# Sheet1.net
KiCad netlist of a schematic drawn in Altium Designer
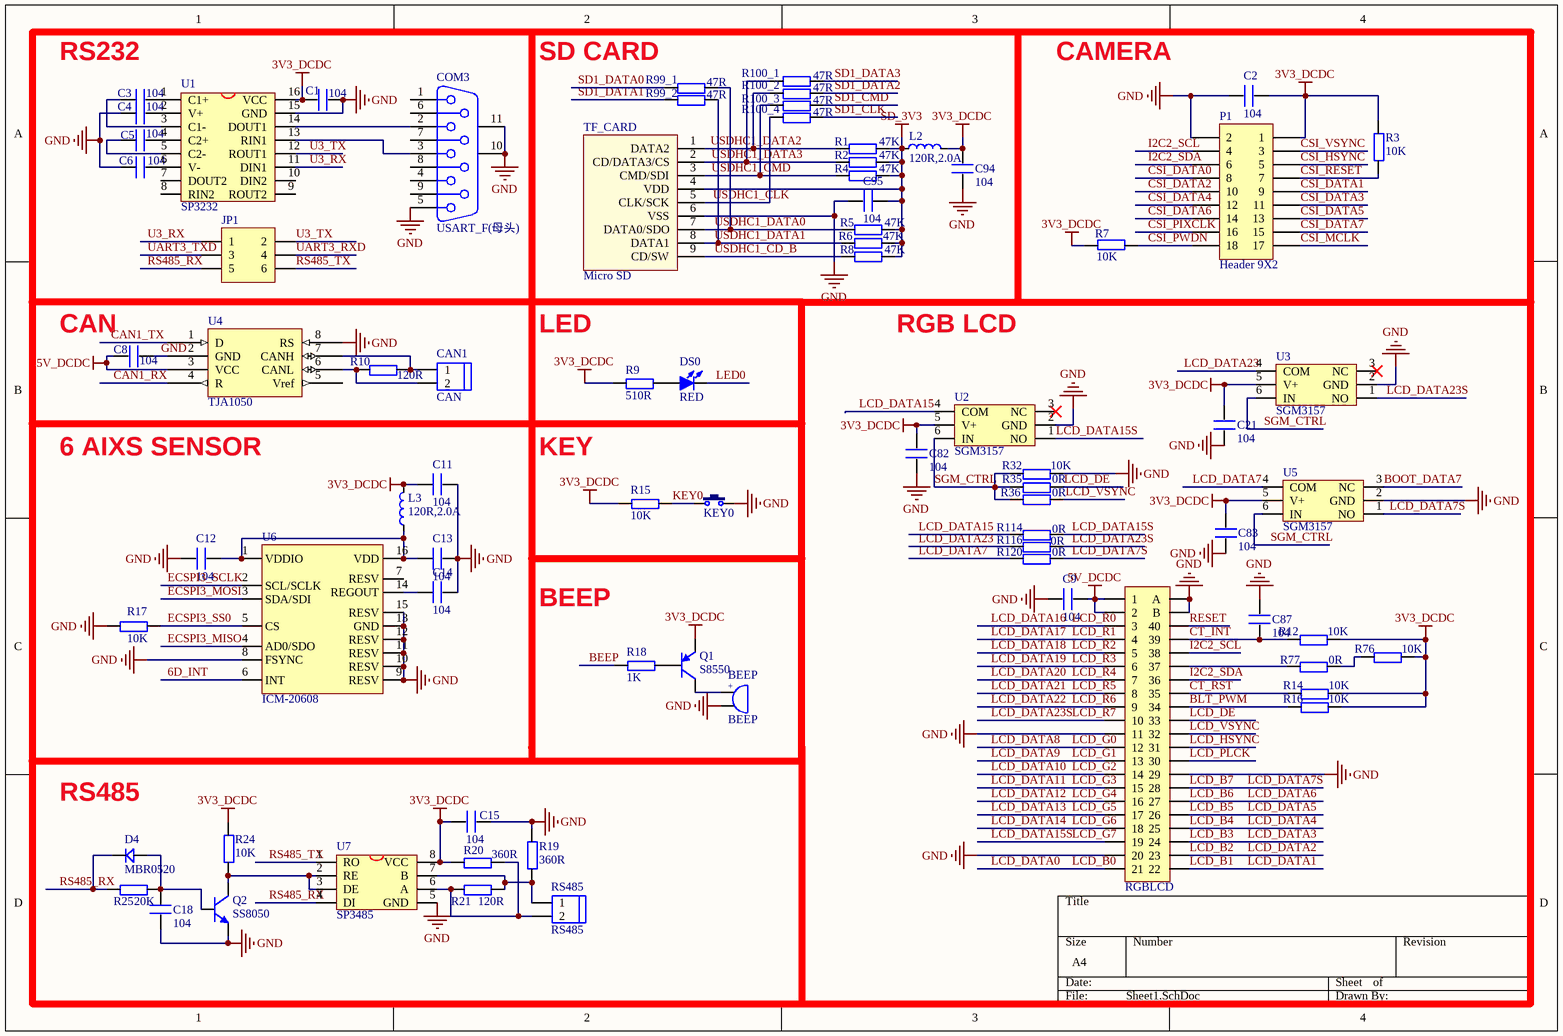
[diagram p0: Sheet1.SchDoc]

(export (version "E")
  (design (tool "Eeschema 10.0.6"))
  (components
    (comp (ref "BEEP")
      (value "BEEP")
      (footprint "BEEP 5x9x5.5")
      (description "蜂鸣器")
      (fields (field (name "版权归属") "源创客"))
      (libsource (lib "linux_board_SCH") (part "BEEP"))
    )
    (comp (ref "C1") (value "104") (footprint "C 0603") (libsource (lib "linux_board_SCH") (part "C")))
    (comp (ref "C2") (value "104") (footprint "C 0603") (libsource (lib "linux_board_SCH") (part "C")))
    (comp (ref "C3") (value "104") (footprint "C 0603") (libsource (lib "linux_board_SCH") (part "C")))
    (comp (ref "C4") (value "104") (footprint "C 0603") (libsource (lib "linux_board_SCH") (part "C")))
    (comp (ref "C5") (value "104") (footprint "C 0603") (libsource (lib "linux_board_SCH") (part "C")))
    (comp (ref "C6") (value "104") (footprint "C 0603") (libsource (lib "linux_board_SCH") (part "C")))
    (comp (ref "C8") (value "104") (footprint "C 0603") (libsource (lib "linux_board_SCH") (part "C")))
    (comp (ref "C9") (value "104") (footprint "C 0603") (libsource (lib "linux_board_SCH") (part "C")))
    (comp (ref "C11") (value "104") (footprint "C 0603") (libsource (lib "linux_board_SCH") (part "C")))
    (comp (ref "C12") (value "104") (footprint "C 0603") (libsource (lib "linux_board_SCH") (part "C")))
    (comp (ref "C13") (value "104") (footprint "C 0603") (libsource (lib "linux_board_SCH") (part "C")))
    (comp (ref "C14") (value "104") (footprint "C 0603") (libsource (lib "linux_board_SCH") (part "C")))
    (comp (ref "C15") (value "104") (footprint "C 0603") (libsource (lib "linux_board_SCH") (part "C")))
    (comp (ref "C18") (value "104") (footprint "C 0603") (libsource (lib "linux_board_SCH") (part "C")))
    (comp (ref "C21") (value "104") (footprint "C 0603") (libsource (lib "linux_board_SCH") (part "C")))
    (comp (ref "C82") (value "104") (footprint "C 0603") (libsource (lib "linux_board_SCH") (part "C")))
    (comp (ref "C83") (value "104") (footprint "C 0603") (libsource (lib "linux_board_SCH") (part "C")))
    (comp (ref "C87") (value "104") (footprint "C 0603") (libsource (lib "linux_board_SCH") (part "C")))
    (comp (ref "C94") (value "104") (footprint "C 0603") (libsource (lib "linux_board_SCH") (part "C")))
    (comp (ref "C95") (value "104") (footprint "C 0603") (libsource (lib "linux_board_SCH") (part "C")))
    (comp (ref "CAN1")
      (value "CAN")
      (footprint "KF301-2P")
      (libsource (lib "linux_board_SCH") (part "HEAD2"))
    )
    (comp (ref "COM3")
      (value "USART_F(母头)")
      (footprint "DB9/P_A")
      (description "9针串口")
      (fields (field (name "版权归属") "源创客"))
      (libsource (lib "linux_board_SCH") (part "DB9"))
    )
    (comp (ref "D4")
      (value "MBR0520")
      (footprint "SOD-123F")
      (description "肖特基二极管")
      (fields (field (name "版权归属") "源创客"))
      (libsource (lib "linux_board_SCH") (part "SS14"))
    )
    (comp (ref "DS0")
      (value "RED")
      (footprint "LED 0805R")
      (description "贴片LED")
      (fields (field (name "版权归属") "源创客"))
      (libsource (lib "linux_board_SCH") (part "LED-SMD"))
    )
    (comp (ref "JP1")
      (value "RS232/RS485")
      (footprint "HDR-3X2")
      (description "3*2P接插件")
      (fields (field (name "版权归属") "源创客"))
      (libsource (lib "linux_board_SCH") (part "Header 3X2"))
    )
    (comp (ref "KEY0")
      (value "KEY")
      (footprint "TSW DIP-6*6*5 - 2")
      (description "按键")
      (fields (field (name "版权归属") "源创客"))
      (libsource (lib "linux_board_SCH") (part "KEY"))
    )
    (comp (ref "L2")
      (value "120R,2.0A")
      (footprint "L 0603")
      (description "小功率贴片电感磁珠")
      (fields (field (name "版权归属") "源创客"))
      (libsource (lib "linux_board_SCH") (part "L"))
    )
    (comp (ref "L3")
      (value "120R,2.0A")
      (footprint "L 0603")
      (description "小功率贴片电感磁珠")
      (fields (field (name "版权归属") "源创客"))
      (libsource (lib "linux_board_SCH") (part "L"))
    )
    (comp (ref "P1")
      (value "Header 9X2")
      (footprint "HDR2X9")
      (description "Header, 9-Pin, Dual row")
      (fields (field (name "PUBLISHER") "Altium Limited"))
      (libsource (lib "linux_board_SCH") (part "Header 9X2"))
    )
    (comp (ref "Q1")
      (value "S8550")
      (footprint "SOT23-3L")
      (description "高频放大-PNP型")
      (fields (field (name "版权归属") "源创客"))
      (libsource (lib "linux_board_SCH") (part "8550-SMD"))
    )
    (comp (ref "Q2")
      (value "SS8050")
      (footprint "SOT23-3N")
      (description "高频放大-NPN型")
      (fields (field (name "版权归属") "源创客"))
      (libsource (lib "linux_board_SCH") (part "8050-SMD"))
    )
    (comp (ref "R1") (value "47K") (footprint "R 0603") (libsource (lib "linux_board_SCH") (part "R")))
    (comp (ref "R2") (value "47K") (footprint "R 0603") (libsource (lib "linux_board_SCH") (part "R")))
    (comp (ref "R3") (value "10K") (footprint "R 0603") (libsource (lib "linux_board_SCH") (part "R")))
    (comp (ref "R4") (value "47K") (footprint "R 0603") (libsource (lib "linux_board_SCH") (part "R")))
    (comp (ref "R5") (value "47K") (footprint "R 0603") (libsource (lib "linux_board_SCH") (part "R")))
    (comp (ref "R6") (value "47K") (footprint "R 0603") (libsource (lib "linux_board_SCH") (part "R")))
    (comp (ref "R7") (value "10K") (footprint "R 0603") (libsource (lib "linux_board_SCH") (part "R")))
    (comp (ref "R8") (value "47K") (footprint "R 0603") (libsource (lib "linux_board_SCH") (part "R")))
    (comp (ref "R9") (value "510R") (footprint "R 0603") (libsource (lib "linux_board_SCH") (part "R")))
    (comp (ref "R10") (value "120R") (footprint "R 0603") (libsource (lib "linux_board_SCH") (part "R")))
    (comp (ref "R12") (value "10K") (footprint "R 0603") (libsource (lib "linux_board_SCH") (part "R")))
    (comp (ref "R14") (value "10K") (footprint "R 0603") (libsource (lib "linux_board_SCH") (part "R")))
    (comp (ref "R15") (value "10K") (footprint "R 0603") (libsource (lib "linux_board_SCH") (part "R")))
    (comp (ref "R16") (value "10K") (footprint "R 0603") (libsource (lib "linux_board_SCH") (part "R")))
    (comp (ref "R17") (value "10K") (footprint "R 0603") (libsource (lib "linux_board_SCH") (part "R")))
    (comp (ref "R18") (value "1K") (footprint "R 0603") (libsource (lib "linux_board_SCH") (part "R")))
    (comp (ref "R19") (value "360R") (footprint "R 0603") (libsource (lib "linux_board_SCH") (part "R")))
    (comp (ref "R20") (value "360R") (footprint "R 0603") (libsource (lib "linux_board_SCH") (part "R")))
    (comp (ref "R21") (value "120R") (footprint "R 0603") (libsource (lib "linux_board_SCH") (part "R")))
    (comp (ref "R24") (value "10K") (footprint "R 0603") (libsource (lib "linux_board_SCH") (part "R")))
    (comp (ref "R25") (value "20K") (footprint "R 0603") (libsource (lib "linux_board_SCH") (part "R")))
    (comp (ref "R32") (value "10K") (footprint "R 0603") (libsource (lib "linux_board_SCH") (part "R")))
    (comp (ref "R35") (value "0R") (footprint "R 0603") (libsource (lib "linux_board_SCH") (part "R")))
    (comp (ref "R36") (value "0R") (footprint "R 0603") (libsource (lib "linux_board_SCH") (part "R")))
    (comp (ref "R76") (value "10K") (footprint "R 0603") (libsource (lib "linux_board_SCH") (part "R")))
    (comp (ref "R77") (value "0R") (footprint "R 0603") (libsource (lib "linux_board_SCH") (part "R")))
    (comp (ref "R99_1") (value "47R") (footprint "R 0603") (libsource (lib "linux_board_SCH") (part "R")))
    (comp (ref "R99_2") (value "47R") (footprint "R 0603") (libsource (lib "linux_board_SCH") (part "R")))
    (comp (ref "R100_1") (value "47R") (footprint "R 0603") (libsource (lib "linux_board_SCH") (part "R")))
    (comp (ref "R100_2") (value "47R") (footprint "R 0603") (libsource (lib "linux_board_SCH") (part "R")))
    (comp (ref "R100_3") (value "47R") (footprint "R 0603") (libsource (lib "linux_board_SCH") (part "R")))
    (comp (ref "R100_4") (value "47R") (footprint "R 0603") (libsource (lib "linux_board_SCH") (part "R")))
    (comp (ref "R114") (value "0R") (footprint "R 0603") (libsource (lib "linux_board_SCH") (part "R")))
    (comp (ref "R116") (value "0R") (footprint "R 0603") (libsource (lib "linux_board_SCH") (part "R")))
    (comp (ref "R120") (value "0R") (footprint "R 0603") (libsource (lib "linux_board_SCH") (part "R")))
    (comp (ref "RGBLCD")
      (value "RGBLCD")
      (footprint "FPC0.5-TOP40P")
      (description "16*2P接插件")
      (fields (field (name "版权归属") "源创客"))
      (libsource (lib "linux_board_SCH") (part "RGBLCD"))
    )
    (comp (ref "RS485")
      (value "RS485")
      (footprint "KF301-2P")
      (libsource (lib "linux_board_SCH") (part "HEAD2"))
    )
    (comp (ref "TF_CARD")
      (value "Micro SD")
      (footprint "Micro SD")
      (description "Micro SD卡")
      (fields (field (name "版权归属") "源创客"))
      (libsource (lib "linux_board_SCH") (part "Micro SD"))
    )
    (comp (ref "U1")
      (value "SP3232")
      (footprint "SOP16_N")
      (libsource (lib "linux_board_SCH") (part "MAX3232"))
    )
    (comp (ref "U2")
      (value "SGM3157")
      (footprint "SOT363-6L")
      (description "单路双掷模拟开关")
      (libsource (lib "linux_board_SCH") (part "SGM3157"))
    )
    (comp (ref "U3")
      (value "SGM3157")
      (footprint "SOT363-6L")
      (description "单路双掷模拟开关")
      (libsource (lib "linux_board_SCH") (part "SGM3157"))
    )
    (comp (ref "U4")
      (value "TJA1050")
      (footprint "SOP8_N")
      (libsource (lib "linux_board_SCH") (part "SN65HVD230D"))
    )
    (comp (ref "U5")
      (value "SGM3157")
      (footprint "SOT363-6L")
      (description "单路双掷模拟开关")
      (libsource (lib "linux_board_SCH") (part "SGM3157"))
    )
    (comp (ref "U6")
      (value "ICM-20608")
      (footprint "LGA-16-3*3*0.75")
      (description "三轴陀螺仪/三轴加速度计,")
      (libsource (lib "linux_board_SCH") (part "ICM20608"))
    )
    (comp (ref "U7")
      (value "SP3485")
      (footprint "SOP8_N")
      (libsource (lib "linux_board_SCH") (part "MAX3485"))
    )
  )
  (nets
    (net (code "1") (name "/6D_INT") (class "Default")
      (node (ref "U6") (pin "6") (pinfunction "INT_6") (pintype "passive"))
    )
    (net (code "2") (name "/BEEP") (class "Default") (node (ref "R18") (pin "1") (pintype "passive")))
    (net (code "3") (name "/BLT_PWM") (class "Default")
      (node (ref "R16") (pin "1") (pintype "passive"))
      (node (ref "RGBLCD") (pin "34") (pinfunction "34_34") (pintype "passive"))
    )
    (net (code "4") (name "/BOOT_DATA7") (class "Default")
      (node (ref "U5") (pin "3") (pinfunction "NC_3") (pintype "passive"))
    )
    (net (code "5") (name "/CAN1_RX") (class "Default")
      (node (ref "U4") (pin "4") (pinfunction "R_4") (pintype "output"))
    )
    (net (code "6") (name "/CAN1_TX") (class "Default")
      (node (ref "U4") (pin "1") (pinfunction "D_1") (pintype "input"))
    )
    (net (code "7") (name "/CSI_DATA0") (class "Default")
      (node (ref "P1") (pin "8") (pinfunction "8_8") (pintype "passive"))
    )
    (net (code "8") (name "/CSI_DATA1") (class "Default")
      (node (ref "P1") (pin "9") (pinfunction "9_9") (pintype "passive"))
    )
    (net (code "9") (name "/CSI_DATA2") (class "Default")
      (node (ref "P1") (pin "10") (pinfunction "10_10") (pintype "passive"))
    )
    (net (code "10") (name "/CSI_DATA3") (class "Default")
      (node (ref "P1") (pin "11") (pinfunction "11_11") (pintype "passive"))
    )
    (net (code "11") (name "/CSI_DATA4") (class "Default")
      (node (ref "P1") (pin "12") (pinfunction "12_12") (pintype "passive"))
    )
    (net (code "12") (name "/CSI_DATA5") (class "Default")
      (node (ref "P1") (pin "13") (pinfunction "13_13") (pintype "passive"))
    )
    (net (code "13") (name "/CSI_DATA6") (class "Default")
      (node (ref "P1") (pin "14") (pinfunction "14_14") (pintype "passive"))
    )
    (net (code "14") (name "/CSI_DATA7") (class "Default")
      (node (ref "P1") (pin "15") (pinfunction "15_15") (pintype "passive"))
    )
    (net (code "15") (name "/CSI_HSYNC") (class "Default")
      (node (ref "P1") (pin "5") (pinfunction "5_5") (pintype "passive"))
    )
    (net (code "16") (name "/CSI_MCLK") (class "Default")
      (node (ref "P1") (pin "17") (pinfunction "17_17") (pintype "passive"))
    )
    (net (code "17") (name "/CSI_PIXCLK") (class "Default")
      (node (ref "P1") (pin "16") (pinfunction "16_16") (pintype "passive"))
    )
    (net (code "18") (name "/CSI_PWDN") (class "Default")
      (node (ref "P1") (pin "18") (pinfunction "18_18") (pintype "passive"))
      (node (ref "R7") (pin "1") (pintype "passive"))
    )
    (net (code "19") (name "/CSI_RESET") (class "Default")
      (node (ref "P1") (pin "7") (pinfunction "7_7") (pintype "passive"))
      (node (ref "R3") (pin "1") (pintype "passive"))
    )
    (net (code "20") (name "/CSI_VSYNC") (class "Default")
      (node (ref "P1") (pin "3") (pinfunction "3_3") (pintype "passive"))
    )
    (net (code "21") (name "/CT_INT") (class "Default")
      (node (ref "C87") (pin "2") (pinfunction "2_2") (pintype "passive"))
      (node (ref "R12") (pin "1") (pintype "passive"))
      (node (ref "RGBLCD") (pin "39") (pinfunction "39_39") (pintype "passive"))
    )
    (net (code "22") (name "/CT_RST") (class "Default")
      (node (ref "R14") (pin "1") (pintype "passive"))
      (node (ref "RGBLCD") (pin "35") (pinfunction "35_35") (pintype "passive"))
    )
    (net (code "23") (name "/ECSPI3_MISO") (class "Default")
      (node (ref "U6") (pin "4") (pinfunction "AD0/SDO_4") (pintype "passive"))
    )
    (net (code "24") (name "/ECSPI3_MOSI") (class "Default")
      (node (ref "U6") (pin "3") (pinfunction "SDA/SDI_3") (pintype "passive"))
    )
    (net (code "25") (name "/ECSPI3_SCLK") (class "Default")
      (node (ref "U6") (pin "2") (pinfunction "SCL/SCLK_2") (pintype "passive"))
    )
    (net (code "26") (name "/ECSPI3_SS0") (class "Default")
      (node (ref "R17") (pin "2") (pintype "passive"))
      (node (ref "U6") (pin "5") (pinfunction "CS_5") (pintype "passive"))
    )
    (net (code "27") (name "/I2C2_SCL") (class "Default")
      (node (ref "P1") (pin "4") (pinfunction "4_4") (pintype "passive"))
      (node (ref "RGBLCD") (pin "38") (pinfunction "38_38") (pintype "passive"))
    )
    (net (code "28") (name "/I2C2_SDA") (class "Default")
      (node (ref "P1") (pin "6") (pinfunction "6_6") (pintype "passive"))
      (node (ref "RGBLCD") (pin "36") (pinfunction "36_36") (pintype "passive"))
    )
    (net (code "29") (name "/KEY0") (class "Default")
      (node (ref "KEY0") (pin "1") (pinfunction "1_1") (pintype "passive"))
      (node (ref "R15") (pin "2") (pintype "passive"))
    )
    (net (code "30") (name "/LCD_B0") (class "Default")
      (node (ref "RGBLCD") (pin "21") (pinfunction "21_21") (pintype "passive"))
    )
    (net (code "31") (name "/LCD_B1") (class "Default")
      (node (ref "RGBLCD") (pin "22") (pinfunction "22_22") (pintype "passive"))
    )
    (net (code "32") (name "/LCD_B2") (class "Default")
      (node (ref "RGBLCD") (pin "23") (pinfunction "23_23") (pintype "passive"))
    )
    (net (code "33") (name "/LCD_B3") (class "Default")
      (node (ref "RGBLCD") (pin "24") (pinfunction "24_24") (pintype "passive"))
    )
    (net (code "34") (name "/LCD_B4") (class "Default")
      (node (ref "RGBLCD") (pin "25") (pinfunction "25_25") (pintype "passive"))
    )
    (net (code "35") (name "/LCD_B5") (class "Default")
      (node (ref "RGBLCD") (pin "26") (pinfunction "26_26") (pintype "passive"))
    )
    (net (code "36") (name "/LCD_B6") (class "Default")
      (node (ref "RGBLCD") (pin "27") (pinfunction "27_27") (pintype "passive"))
    )
    (net (code "37") (name "/LCD_B7") (class "Default")
      (node (ref "R120") (pin "2") (pintype "passive"))
      (node (ref "RGBLCD") (pin "28") (pinfunction "28_28") (pintype "passive"))
      (node (ref "U5") (pin "1") (pinfunction "NO_1") (pintype "passive"))
    )
    (net (code "38") (name "/LCD_DATA7") (class "Default")
      (node (ref "R120") (pin "1") (pintype "passive"))
      (node (ref "U5") (pin "4") (pinfunction "COM_4") (pintype "passive"))
    )
    (net (code "39") (name "/LCD_DATA8") (class "Default")
      (node (ref "RGBLCD") (pin "12") (pinfunction "12_12") (pintype "passive"))
    )
    (net (code "40") (name "/LCD_DATA9") (class "Default")
      (node (ref "RGBLCD") (pin "13") (pinfunction "13_13") (pintype "passive"))
    )
    (net (code "41") (name "/LCD_DATA10") (class "Default")
      (node (ref "RGBLCD") (pin "14") (pinfunction "14_14") (pintype "passive"))
    )
    (net (code "42") (name "/LCD_DATA11") (class "Default")
      (node (ref "RGBLCD") (pin "15") (pinfunction "15_15") (pintype "passive"))
    )
    (net (code "43") (name "/LCD_DATA12") (class "Default")
      (node (ref "RGBLCD") (pin "16") (pinfunction "16_16") (pintype "passive"))
    )
    (net (code "44") (name "/LCD_DATA13") (class "Default")
      (node (ref "RGBLCD") (pin "17") (pinfunction "17_17") (pintype "passive"))
    )
    (net (code "45") (name "/LCD_DATA14") (class "Default")
      (node (ref "RGBLCD") (pin "18") (pinfunction "18_18") (pintype "passive"))
    )
    (net (code "46") (name "/LCD_DATA15") (class "Default")
      (node (ref "R114") (pin "1") (pintype "passive"))
      (node (ref "U2") (pin "4") (pinfunction "COM_4") (pintype "passive"))
    )
    (net (code "47") (name "/LCD_DATA15S") (class "Default")
      (node (ref "R114") (pin "2") (pintype "passive"))
      (node (ref "RGBLCD") (pin "19") (pinfunction "19_19") (pintype "passive"))
      (node (ref "U2") (pin "1") (pinfunction "NO_1") (pintype "passive"))
    )
    (net (code "48") (name "/LCD_DATA16") (class "Default")
      (node (ref "RGBLCD") (pin "3") (pinfunction "3_3") (pintype "passive"))
    )
    (net (code "49") (name "/LCD_DATA17") (class "Default")
      (node (ref "RGBLCD") (pin "4") (pinfunction "4_4") (pintype "passive"))
    )
    (net (code "50") (name "/LCD_DATA18") (class "Default")
      (node (ref "RGBLCD") (pin "5") (pinfunction "5_5") (pintype "passive"))
    )
    (net (code "51") (name "/LCD_DATA19") (class "Default")
      (node (ref "RGBLCD") (pin "6") (pinfunction "6_6") (pintype "passive"))
    )
    (net (code "52") (name "/LCD_DATA20") (class "Default")
      (node (ref "RGBLCD") (pin "7") (pinfunction "7_7") (pintype "passive"))
    )
    (net (code "53") (name "/LCD_DATA21") (class "Default")
      (node (ref "RGBLCD") (pin "8") (pinfunction "8_8") (pintype "passive"))
    )
    (net (code "54") (name "/LCD_DATA22") (class "Default")
      (node (ref "RGBLCD") (pin "9") (pinfunction "9_9") (pintype "passive"))
    )
    (net (code "55") (name "/LCD_DATA23") (class "Default")
      (node (ref "R116") (pin "1") (pintype "passive"))
      (node (ref "U3") (pin "4") (pinfunction "COM_4") (pintype "passive"))
    )
    (net (code "56") (name "/LCD_DATA23S") (class "Default")
      (node (ref "R116") (pin "2") (pintype "passive"))
      (node (ref "RGBLCD") (pin "10") (pinfunction "10_10") (pintype "passive"))
      (node (ref "U3") (pin "1") (pinfunction "NO_1") (pintype "passive"))
    )
    (net (code "57") (name "/LCD_DE") (class "Default")
      (node (ref "R35") (pin "2") (pintype "passive"))
      (node (ref "RGBLCD") (pin "33") (pinfunction "33_33") (pintype "passive"))
    )
    (net (code "58") (name "/LCD_HSYNC") (class "Default")
      (node (ref "RGBLCD") (pin "31") (pinfunction "31_31") (pintype "passive"))
    )
    (net (code "59") (name "/LCD_PLCK") (class "Default")
      (node (ref "RGBLCD") (pin "30") (pinfunction "30_30") (pintype "passive"))
    )
    (net (code "60") (name "/LCD_VSYNC") (class "Default")
      (node (ref "R36") (pin "2") (pintype "passive"))
      (node (ref "RGBLCD") (pin "32") (pinfunction "32_32") (pintype "passive"))
    )
    (net (code "61") (name "/LED0") (class "Default")
      (node (ref "DS0") (pin "2") (pinfunction "K_2") (pintype "passive"))
    )
    (net (code "62") (name "/RESET") (class "Default")
      (node (ref "RGBLCD") (pin "40") (pinfunction "40_40") (pintype "passive"))
    )
    (net (code "63") (name "/RS485_RX") (class "Default")
      (node (ref "D4") (pin "2") (pinfunction "K_2") (pintype "passive"))
      (node (ref "JP1") (pin "5") (pinfunction "5_5") (pintype "passive"))
      (node (ref "R25") (pin "1") (pintype "passive"))
      (node (ref "U7") (pin "4") (pinfunction "DI_4") (pintype "passive"))
    )
    (net (code "64") (name "/RS485_TX") (class "Default")
      (node (ref "JP1") (pin "6") (pinfunction "6_6") (pintype "passive"))
      (node (ref "U7") (pin "1") (pinfunction "RO_1") (pintype "passive"))
    )
    (net (code "65") (name "/SD1_CLK") (class "Default") (node (ref "R100_4") (pin "2") (pintype "passive")))
    (net (code "66") (name "/SD1_CMD") (class "Default") (node (ref "R100_3") (pin "2") (pintype "passive")))
    (net (code "67") (name "/SD1_DATA0") (class "Default") (node (ref "R99_1") (pin "1") (pintype "passive")))
    (net (code "68") (name "/SD1_DATA1") (class "Default") (node (ref "R99_2") (pin "1") (pintype "passive")))
    (net (code "69") (name "/SD1_DATA2") (class "Default")
      (node (ref "R100_2") (pin "2") (pintype "passive"))
    )
    (net (code "70") (name "/SD1_DATA3") (class "Default")
      (node (ref "R100_1") (pin "2") (pintype "passive"))
    )
    (net (code "71") (name "/SGM_CTRL") (class "Default")
      (node (ref "R32") (pin "1") (pintype "passive"))
      (node (ref "R35") (pin "1") (pintype "passive"))
      (node (ref "R36") (pin "1") (pintype "passive"))
      (node (ref "U2") (pin "6") (pinfunction "IN_6") (pintype "passive"))
      (node (ref "U3") (pin "6") (pinfunction "IN_6") (pintype "passive"))
      (node (ref "U5") (pin "6") (pinfunction "IN_6") (pintype "passive"))
    )
    (net (code "72") (name "/U3_RX") (class "Default")
      (node (ref "JP1") (pin "1") (pinfunction "1_1") (pintype "passive"))
      (node (ref "U1") (pin "11") (pinfunction "DIN1_11") (pintype "passive"))
    )
    (net (code "73") (name "/U3_TX") (class "Default")
      (node (ref "JP1") (pin "2") (pinfunction "2_2") (pintype "passive"))
      (node (ref "U1") (pin "12") (pinfunction "ROUT1_12") (pintype "passive"))
    )
    (net (code "74") (name "/UART3_RXD") (class "Default")
      (node (ref "JP1") (pin "4") (pinfunction "4_4") (pintype "passive"))
    )
    (net (code "75") (name "/UART3_TXD") (class "Default")
      (node (ref "JP1") (pin "3") (pinfunction "3_3") (pintype "passive"))
    )
    (net (code "76") (name "/USDHC1_CD_B") (class "Default")
      (node (ref "R8") (pin "1") (pintype "passive"))
      (node (ref "TF_CARD") (pin "9") (pinfunction "CD/SW_9") (pintype "passive"))
    )
    (net (code "77") (name "/USDHC1_CLK") (class "Default")
      (node (ref "R100_4") (pin "1") (pintype "passive"))
      (node (ref "TF_CARD") (pin "5") (pinfunction "CLK/SCK_5") (pintype "passive"))
    )
    (net (code "78") (name "/USDHC1_CMD") (class "Default")
      (node (ref "R100_3") (pin "1") (pintype "passive"))
      (node (ref "R4") (pin "1") (pintype "passive"))
      (node (ref "TF_CARD") (pin "3") (pinfunction "CMD/SDI_3") (pintype "passive"))
    )
    (net (code "79") (name "/USDHC1_DATA0") (class "Default")
      (node (ref "R5") (pin "1") (pintype "passive"))
      (node (ref "R99_1") (pin "2") (pintype "passive"))
      (node (ref "TF_CARD") (pin "7") (pinfunction "DATA0/SDO_7") (pintype "passive"))
    )
    (net (code "80") (name "/USDHC1_DATA1") (class "Default")
      (node (ref "R6") (pin "1") (pintype "passive"))
      (node (ref "R99_2") (pin "2") (pintype "passive"))
      (node (ref "TF_CARD") (pin "8") (pinfunction "DATA1_8") (pintype "passive"))
    )
    (net (code "81") (name "/USDHC1_DATA2") (class "Default")
      (node (ref "R1") (pin "1") (pintype "passive"))
      (node (ref "R100_2") (pin "1") (pintype "passive"))
      (node (ref "TF_CARD") (pin "1") (pinfunction "DATA2_1") (pintype "passive"))
    )
    (net (code "82") (name "/USDHC1_DATA3") (class "Default")
      (node (ref "R100_1") (pin "1") (pintype "passive"))
      (node (ref "R2") (pin "1") (pintype "passive"))
      (node (ref "TF_CARD") (pin "2") (pinfunction "CD/DATA3/CS_2") (pintype "passive"))
    )
    (net (code "83") (name "3V3_DCDC") (class "Default")
      (node (ref "C1") (pin "1") (pinfunction "1_1") (pintype "passive"))
      (node (ref "C11") (pin "1") (pinfunction "1_1") (pintype "passive"))
      (node (ref "C15") (pin "1") (pinfunction "1_1") (pintype "passive"))
      (node (ref "C2") (pin "1") (pinfunction "1_1") (pintype "passive"))
      (node (ref "C21") (pin "2") (pinfunction "2_2") (pintype "passive"))
      (node (ref "C82") (pin "2") (pinfunction "2_2") (pintype "passive"))
      (node (ref "C83") (pin "2") (pinfunction "2_2") (pintype "passive"))
      (node (ref "C94") (pin "2") (pinfunction "2_2") (pintype "passive"))
      (node (ref "L2") (pin "2") (pinfunction "2_2") (pintype "passive"))
      (node (ref "L3") (pin "2") (pinfunction "2_2") (pintype "passive"))
      (node (ref "P1") (pin "1") (pinfunction "1_1") (pintype "passive"))
      (node (ref "Q1") (pin "2") (pinfunction "E_2") (pintype "passive"))
      (node (ref "R12") (pin "2") (pintype "passive"))
      (node (ref "R14") (pin "2") (pintype "passive"))
      (node (ref "R15") (pin "1") (pintype "passive"))
      (node (ref "R16") (pin "2") (pintype "passive"))
      (node (ref "R20") (pin "1") (pintype "passive"))
      (node (ref "R24") (pin "2") (pintype "passive"))
      (node (ref "R3") (pin "2") (pintype "passive"))
      (node (ref "R7") (pin "2") (pintype "passive"))
      (node (ref "R76") (pin "2") (pintype "passive"))
      (node (ref "R9") (pin "1") (pintype "passive"))
      (node (ref "U1") (pin "16") (pinfunction "VCC_16") (pintype "passive"))
      (node (ref "U2") (pin "5") (pinfunction "V+_5") (pintype "passive"))
      (node (ref "U3") (pin "5") (pinfunction "V+_5") (pintype "passive"))
      (node (ref "U5") (pin "5") (pinfunction "V+_5") (pintype "passive"))
      (node (ref "U7") (pin "8") (pinfunction "VCC_8") (pintype "passive"))
    )
    (net (code "84") (name "5V_DCDC") (class "Default")
      (node (ref "C8") (pin "1") (pinfunction "1_1") (pintype "passive"))
      (node (ref "C9") (pin "1") (pinfunction "1_1") (pintype "passive"))
      (node (ref "RGBLCD") (pin "1") (pinfunction "1_1") (pintype "passive"))
      (node (ref "RGBLCD") (pin "2") (pinfunction "2_2") (pintype "passive"))
      (node (ref "U4") (pin "3") (pinfunction "VCC_3") (pintype "power_in"))
    )
    (net (code "85") (name "GND") (class "Default")
      (node (ref "BEEP") (pin "2") (pinfunction "2_2") (pintype "passive"))
      (node (ref "C1") (pin "2") (pinfunction "2_2") (pintype "passive"))
      (node (ref "C11") (pin "2") (pinfunction "2_2") (pintype "passive"))
      (node (ref "C12") (pin "1") (pinfunction "1_1") (pintype "passive"))
      (node (ref "C13") (pin "2") (pinfunction "2_2") (pintype "passive"))
      (node (ref "C14") (pin "2") (pinfunction "2_2") (pintype "passive"))
      (node (ref "C15") (pin "2") (pinfunction "2_2") (pintype "passive"))
      (node (ref "C18") (pin "1") (pinfunction "1_1") (pintype "passive"))
      (node (ref "C2") (pin "2") (pinfunction "2_2") (pintype "passive"))
      (node (ref "C21") (pin "1") (pinfunction "1_1") (pintype "passive"))
      (node (ref "C4") (pin "1") (pinfunction "1_1") (pintype "passive"))
      (node (ref "C6") (pin "1") (pinfunction "1_1") (pintype "passive"))
      (node (ref "C8") (pin "2") (pinfunction "2_2") (pintype "passive"))
      (node (ref "C82") (pin "1") (pinfunction "1_1") (pintype "passive"))
      (node (ref "C83") (pin "1") (pinfunction "1_1") (pintype "passive"))
      (node (ref "C87") (pin "1") (pinfunction "1_1") (pintype "passive"))
      (node (ref "C9") (pin "2") (pinfunction "2_2") (pintype "passive"))
      (node (ref "C94") (pin "1") (pinfunction "1_1") (pintype "passive"))
      (node (ref "C95") (pin "1") (pinfunction "1_1") (pintype "passive"))
      (node (ref "COM3") (pin "10") (pinfunction "MH1_10") (pintype "passive"))
      (node (ref "COM3") (pin "11") (pinfunction "MH2_11") (pintype "passive"))
      (node (ref "COM3") (pin "5") (pinfunction "5_5") (pintype "passive"))
      (node (ref "KEY0") (pin "2") (pinfunction "2_2") (pintype "passive"))
      (node (ref "P1") (pin "2") (pinfunction "2_2") (pintype "passive"))
      (node (ref "Q2") (pin "2") (pinfunction "E_2") (pintype "passive"))
      (node (ref "R17") (pin "1") (pintype "passive"))
      (node (ref "R19") (pin "2") (pintype "passive"))
      (node (ref "R32") (pin "2") (pintype "passive"))
      (node (ref "RGBLCD") (pin "11") (pinfunction "11_11") (pintype "passive"))
      (node (ref "RGBLCD") (pin "20") (pinfunction "20_20") (pintype "passive"))
      (node (ref "RGBLCD") (pin "29") (pinfunction "29_29") (pintype "passive"))
      (node (ref "RGBLCD") (pin "41") (pinfunction "B_41") (pintype "passive"))
      (node (ref "RGBLCD") (pin "42") (pinfunction "A_42") (pintype "passive"))
      (node (ref "TF_CARD") (pin "6") (pinfunction "VSS_6") (pintype "passive"))
      (node (ref "U1") (pin "15") (pinfunction "GND_15") (pintype "passive"))
      (node (ref "U2") (pin "2") (pinfunction "GND_2") (pintype "passive"))
      (node (ref "U3") (pin "2") (pinfunction "GND_2") (pintype "passive"))
      (node (ref "U4") (pin "2") (pinfunction "GND_2") (pintype "power_in"))
      (node (ref "U4") (pin "8") (pinfunction "RS_8") (pintype "input"))
      (node (ref "U5") (pin "2") (pinfunction "GND_2") (pintype "passive"))
      (node (ref "U6") (pin "10") (pinfunction "RESV_10") (pintype "passive"))
      (node (ref "U6") (pin "11") (pinfunction "RESV_11") (pintype "passive"))
      (node (ref "U6") (pin "12") (pinfunction "RESV_12") (pintype "passive"))
      (node (ref "U6") (pin "13") (pinfunction "GND_13") (pintype "passive"))
      (node (ref "U6") (pin "15") (pinfunction "RESV_15") (pintype "passive"))
      (node (ref "U6") (pin "8") (pinfunction "FSYNC_8") (pintype "passive"))
      (node (ref "U6") (pin "9") (pinfunction "RESV_9") (pintype "passive"))
      (node (ref "U7") (pin "5") (pinfunction "GND_5") (pintype "passive"))
    )
    (net (code "86") (name "Net-(D4-A)") (class "Default")
      (node (ref "C18") (pin "2") (pinfunction "2_2") (pintype "passive"))
      (node (ref "D4") (pin "1") (pinfunction "A_1") (pintype "passive"))
      (node (ref "Q2") (pin "1") (pinfunction "B_1") (pintype "passive"))
      (node (ref "R25") (pin "2") (pintype "passive"))
    )
    (net (code "87") (name "Net-(DS0-A)") (class "Default")
      (node (ref "DS0") (pin "1") (pinfunction "A_1") (pintype "passive"))
      (node (ref "R9") (pin "2") (pintype "passive"))
    )
    (net (code "88") (name "Net-(Q1-B)") (class "Default")
      (node (ref "Q1") (pin "1") (pinfunction "B_1") (pintype "passive"))
      (node (ref "R18") (pin "2") (pintype "passive"))
    )
    (net (code "89") (name "Net-(Q1-C)") (class "Default")
      (node (ref "BEEP") (pin "1") (pinfunction "1_1") (pintype "passive"))
      (node (ref "Q1") (pin "3") (pinfunction "C_3") (pintype "passive"))
    )
    (net (code "90") (name "Net-(Q2-C)") (class "Default")
      (node (ref "Q2") (pin "3") (pinfunction "C_3") (pintype "passive"))
      (node (ref "R24") (pin "1") (pintype "passive"))
      (node (ref "U7") (pin "2") (pinfunction "RE_2") (pintype "passive"))
      (node (ref "U7") (pin "3") (pinfunction "DE_3") (pintype "passive"))
    )
    (net (code "91") (name "Net-(R76-Pad1)") (class "Default")
      (node (ref "R76") (pin "1") (pintype "passive"))
      (node (ref "R77") (pin "2") (pintype "passive"))
    )
    (net (code "92") (name "Net-(R77-Pad1)") (class "Default")
      (node (ref "R77") (pin "1") (pintype "passive"))
      (node (ref "RGBLCD") (pin "37") (pinfunction "37_37") (pintype "passive"))
    )
    (net (code "93") (name "Net-(U1-C1+)") (class "Default")
      (node (ref "C3") (pin "2") (pinfunction "2_2") (pintype "passive"))
      (node (ref "U1") (pin "1") (pinfunction "C1+_1") (pintype "passive"))
    )
    (net (code "94") (name "Net-(U1-C1-)") (class "Default")
      (node (ref "C3") (pin "1") (pinfunction "1_1") (pintype "passive"))
      (node (ref "U1") (pin "3") (pinfunction "C1-_3") (pintype "passive"))
    )
    (net (code "95") (name "Net-(U1-C2+)") (class "Default")
      (node (ref "C5") (pin "2") (pinfunction "2_2") (pintype "passive"))
      (node (ref "U1") (pin "4") (pinfunction "C2+_4") (pintype "passive"))
    )
    (net (code "96") (name "Net-(U1-C2-)") (class "Default")
      (node (ref "C5") (pin "1") (pinfunction "1_1") (pintype "passive"))
      (node (ref "U1") (pin "5") (pinfunction "C2-_5") (pintype "passive"))
    )
    (net (code "97") (name "Net-(U1-DOUT1)") (class "Default")
      (node (ref "COM3") (pin "2") (pinfunction "2_2") (pintype "passive"))
      (node (ref "U1") (pin "14") (pinfunction "DOUT1_14") (pintype "passive"))
    )
    (net (code "98") (name "Net-(U1-RIN1)") (class "Default")
      (node (ref "COM3") (pin "3") (pinfunction "3_3") (pintype "passive"))
      (node (ref "U1") (pin "13") (pinfunction "RIN1_13") (pintype "passive"))
    )
    (net (code "99") (name "Net-(U1-V+)") (class "Default")
      (node (ref "C4") (pin "2") (pinfunction "2_2") (pintype "passive"))
      (node (ref "U1") (pin "2") (pinfunction "V+_2") (pintype "passive"))
    )
    (net (code "100") (name "Net-(U1-V-)") (class "Default")
      (node (ref "C6") (pin "2") (pinfunction "2_2") (pintype "passive"))
      (node (ref "U1") (pin "6") (pinfunction "V-_6") (pintype "passive"))
    )
    (net (code "101") (name "Net-(U4-CANH)") (class "Default")
      (node (ref "CAN1") (pin "1") (pinfunction "1_1") (pintype "passive"))
      (node (ref "R10") (pin "2") (pintype "passive"))
      (node (ref "U4") (pin "7") (pinfunction "CANH_7") (pintype "bidirectional"))
    )
    (net (code "102") (name "Net-(U4-CANL)") (class "Default")
      (node (ref "CAN1") (pin "2") (pinfunction "2_2") (pintype "passive"))
      (node (ref "R10") (pin "1") (pintype "passive"))
      (node (ref "U4") (pin "6") (pinfunction "CANL_6") (pintype "bidirectional"))
    )
    (net (code "103") (name "Net-(U6-REGOUT)") (class "Default")
      (node (ref "C14") (pin "1") (pinfunction "1_1") (pintype "passive"))
      (node (ref "U6") (pin "14") (pinfunction "REGOUT_14") (pintype "passive"))
    )
    (net (code "104") (name "Net-(U6-VDD)") (class "Default")
      (node (ref "C12") (pin "2") (pinfunction "2_2") (pintype "passive"))
      (node (ref "C13") (pin "1") (pinfunction "1_1") (pintype "passive"))
      (node (ref "L3") (pin "1") (pinfunction "1_1") (pintype "passive"))
      (node (ref "U6") (pin "1") (pinfunction "VDDIO_1") (pintype "passive"))
      (node (ref "U6") (pin "16") (pinfunction "VDD_16") (pintype "passive"))
    )
    (net (code "105") (name "Net-(U7-A)") (class "Default")
      (node (ref "R20") (pin "2") (pintype "passive"))
      (node (ref "R21") (pin "1") (pintype "passive"))
      (node (ref "RS485") (pin "2") (pinfunction "2_2") (pintype "passive"))
      (node (ref "U7") (pin "6") (pinfunction "A_6") (pintype "passive"))
    )
    (net (code "106") (name "Net-(U7-B)") (class "Default")
      (node (ref "R19") (pin "1") (pintype "passive"))
      (node (ref "R21") (pin "2") (pintype "passive"))
      (node (ref "RS485") (pin "1") (pinfunction "1_1") (pintype "passive"))
      (node (ref "U7") (pin "7") (pinfunction "B_7") (pintype "passive"))
    )
    (net (code "107") (name "SD_3V3") (class "Default")
      (node (ref "C95") (pin "2") (pinfunction "2_2") (pintype "passive"))
      (node (ref "L2") (pin "1") (pinfunction "1_1") (pintype "passive"))
      (node (ref "R1") (pin "2") (pintype "passive"))
      (node (ref "R2") (pin "2") (pintype "passive"))
      (node (ref "R4") (pin "2") (pintype "passive"))
      (node (ref "R5") (pin "2") (pintype "passive"))
      (node (ref "R6") (pin "2") (pintype "passive"))
      (node (ref "R8") (pin "2") (pintype "passive"))
      (node (ref "TF_CARD") (pin "4") (pinfunction "VDD_4") (pintype "passive"))
    )
    (net (code "108") (name "unconnected-(COM3-Pad1)") (class "Default")
      (node (ref "COM3") (pin "1") (pinfunction "1_1") (pintype "passive"))
    )
    (net (code "109") (name "unconnected-(COM3-Pad4)") (class "Default")
      (node (ref "COM3") (pin "4") (pinfunction "4_4") (pintype "passive"))
    )
    (net (code "110") (name "unconnected-(COM3-Pad6)") (class "Default")
      (node (ref "COM3") (pin "6") (pinfunction "6_6") (pintype "passive"))
    )
    (net (code "111") (name "unconnected-(COM3-Pad7)") (class "Default")
      (node (ref "COM3") (pin "7") (pinfunction "7_7") (pintype "passive"))
    )
    (net (code "112") (name "unconnected-(COM3-Pad8)") (class "Default")
      (node (ref "COM3") (pin "8") (pinfunction "8_8") (pintype "passive"))
    )
    (net (code "113") (name "unconnected-(COM3-Pad9)") (class "Default")
      (node (ref "COM3") (pin "9") (pinfunction "9_9") (pintype "passive"))
    )
    (net (code "114") (name "unconnected-(U1-DIN2-Pad10)") (class "Default")
      (node (ref "U1") (pin "10") (pinfunction "DIN2_10") (pintype "passive"))
    )
    (net (code "115") (name "unconnected-(U1-DOUT2-Pad7)") (class "Default")
      (node (ref "U1") (pin "7") (pinfunction "DOUT2_7") (pintype "passive"))
    )
    (net (code "116") (name "unconnected-(U1-RIN2-Pad8)") (class "Default")
      (node (ref "U1") (pin "8") (pinfunction "RIN2_8") (pintype "passive"))
    )
    (net (code "117") (name "unconnected-(U1-ROUT2-Pad9)") (class "Default")
      (node (ref "U1") (pin "9") (pinfunction "ROUT2_9") (pintype "passive"))
    )
    (net (code "118") (name "unconnected-(U2-NC-Pad3)") (class "Default")
      (node (ref "U2") (pin "3") (pinfunction "NC_3") (pintype "passive+no_connect"))
    )
    (net (code "119") (name "unconnected-(U3-NC-Pad3)") (class "Default")
      (node (ref "U3") (pin "3") (pinfunction "NC_3") (pintype "passive+no_connect"))
    )
    (net (code "120") (name "unconnected-(U4-Vref-Pad5)") (class "Default")
      (node (ref "U4") (pin "5") (pinfunction "Vref_5") (pintype "output"))
    )
    (net (code "121") (name "unconnected-(U6-RESV-Pad7)") (class "Default")
      (node (ref "U6") (pin "7") (pinfunction "RESV_7") (pintype "passive"))
    )
  )
)
